# Via_Stitching_and_Shielding.net
KiCad netlist of a schematic drawn in Altium Designer
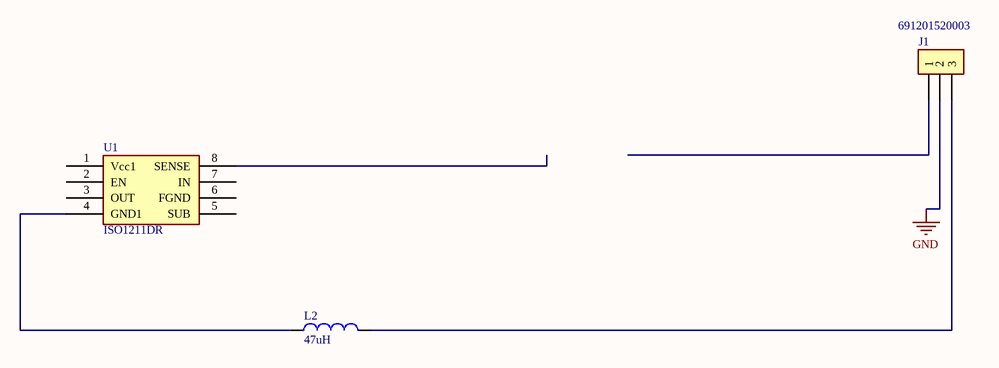
[diagram p0: Via Stitching and Shielding.SchDoc]

(export (version "E")
  (design (tool "Eeschema 10.0.6"))
  (components
    (comp (ref "J1")
      (value "691201520003")
      (footprint "CLEMA 3X1")
      (description "No. Parte: 691201520003, Pitch 5.08 mm - 45° , Wurth Eectronics")
      (libsource (lib "Metro PA-M50") (part "CLEMA 3X1 Wurth Eectronics"))
    )
    (comp (ref "L2")
      (value "47uH")
      (footprint "IND-4.8X4.8mm")
      (description "FIXED IND 47UH 0.8A 270 MOHM SMD")
      (fields
        (field (name "MANUFACTURER") "Bourns")
        (field (name "MANUFACTURER PART NUMBER") "SRR4828A-470M")
      )
      (libsource (lib "Metro PA-M50") (part "IND-47uH/800mA"))
    )
    (comp (ref "U1")
      (value "ISO1211DR")
      (footprint "SOIC8")
      (description "24-V to 60-V Digital Input Receivers for Digital Input Modules datasheet")
      (fields (field (name "MANUFACTURER") "Texas Instruments"))
      (libsource (lib "Metro PA-M50") (part "AisladorDig-ISO1211DR"))
    )
  )
  (nets
    (net (code "1") (name "GND") (class "Default")
      (node (ref "J1") (pin "2") (pinfunction "2_2") (pintype "passive"))
    )
    (net (code "2") (name "Net-(J1-Pad3)") (class "Default")
      (node (ref "J1") (pin "3") (pinfunction "3_3") (pintype "passive"))
      (node (ref "L2") (pin "2") (pinfunction "2_2") (pintype "passive"))
    )
    (net (code "3") (name "Net-(U1-GND1)") (class "Default")
      (node (ref "L2") (pin "1") (pinfunction "1_1") (pintype "passive"))
      (node (ref "U1") (pin "4") (pinfunction "GND1_4") (pintype "passive"))
    )
    (net (code "4") (name "unconnected-(J1-Pad1)") (class "Default")
      (node (ref "J1") (pin "1") (pinfunction "1_1") (pintype "passive"))
    )
    (net (code "5") (name "unconnected-(U1-EN-Pad2)") (class "Default")
      (node (ref "U1") (pin "2") (pinfunction "EN_2") (pintype "passive"))
    )
    (net (code "6") (name "unconnected-(U1-FGND-Pad6)") (class "Default")
      (node (ref "U1") (pin "6") (pinfunction "FGND_6") (pintype "passive"))
    )
    (net (code "7") (name "unconnected-(U1-IN-Pad7)") (class "Default")
      (node (ref "U1") (pin "7") (pinfunction "IN_7") (pintype "passive"))
    )
    (net (code "8") (name "unconnected-(U1-OUT-Pad3)") (class "Default")
      (node (ref "U1") (pin "3") (pinfunction "OUT_3") (pintype "passive"))
    )
    (net (code "9") (name "unconnected-(U1-SENSE-Pad8)") (class "Default")
      (node (ref "U1") (pin "8") (pinfunction "SENSE_8") (pintype "passive"))
    )
    (net (code "10") (name "unconnected-(U1-SUB-Pad5)") (class "Default")
      (node (ref "U1") (pin "5") (pinfunction "SUB_5") (pintype "passive"))
    )
    (net (code "11") (name "unconnected-(U1-Vcc1-Pad1)") (class "Default")
      (node (ref "U1") (pin "1") (pinfunction "Vcc1_1") (pintype "passive"))
    )
  )
)
